# FMU_FMU_REV_1A.net
KiCad netlist of a schematic drawn in Altium Designer
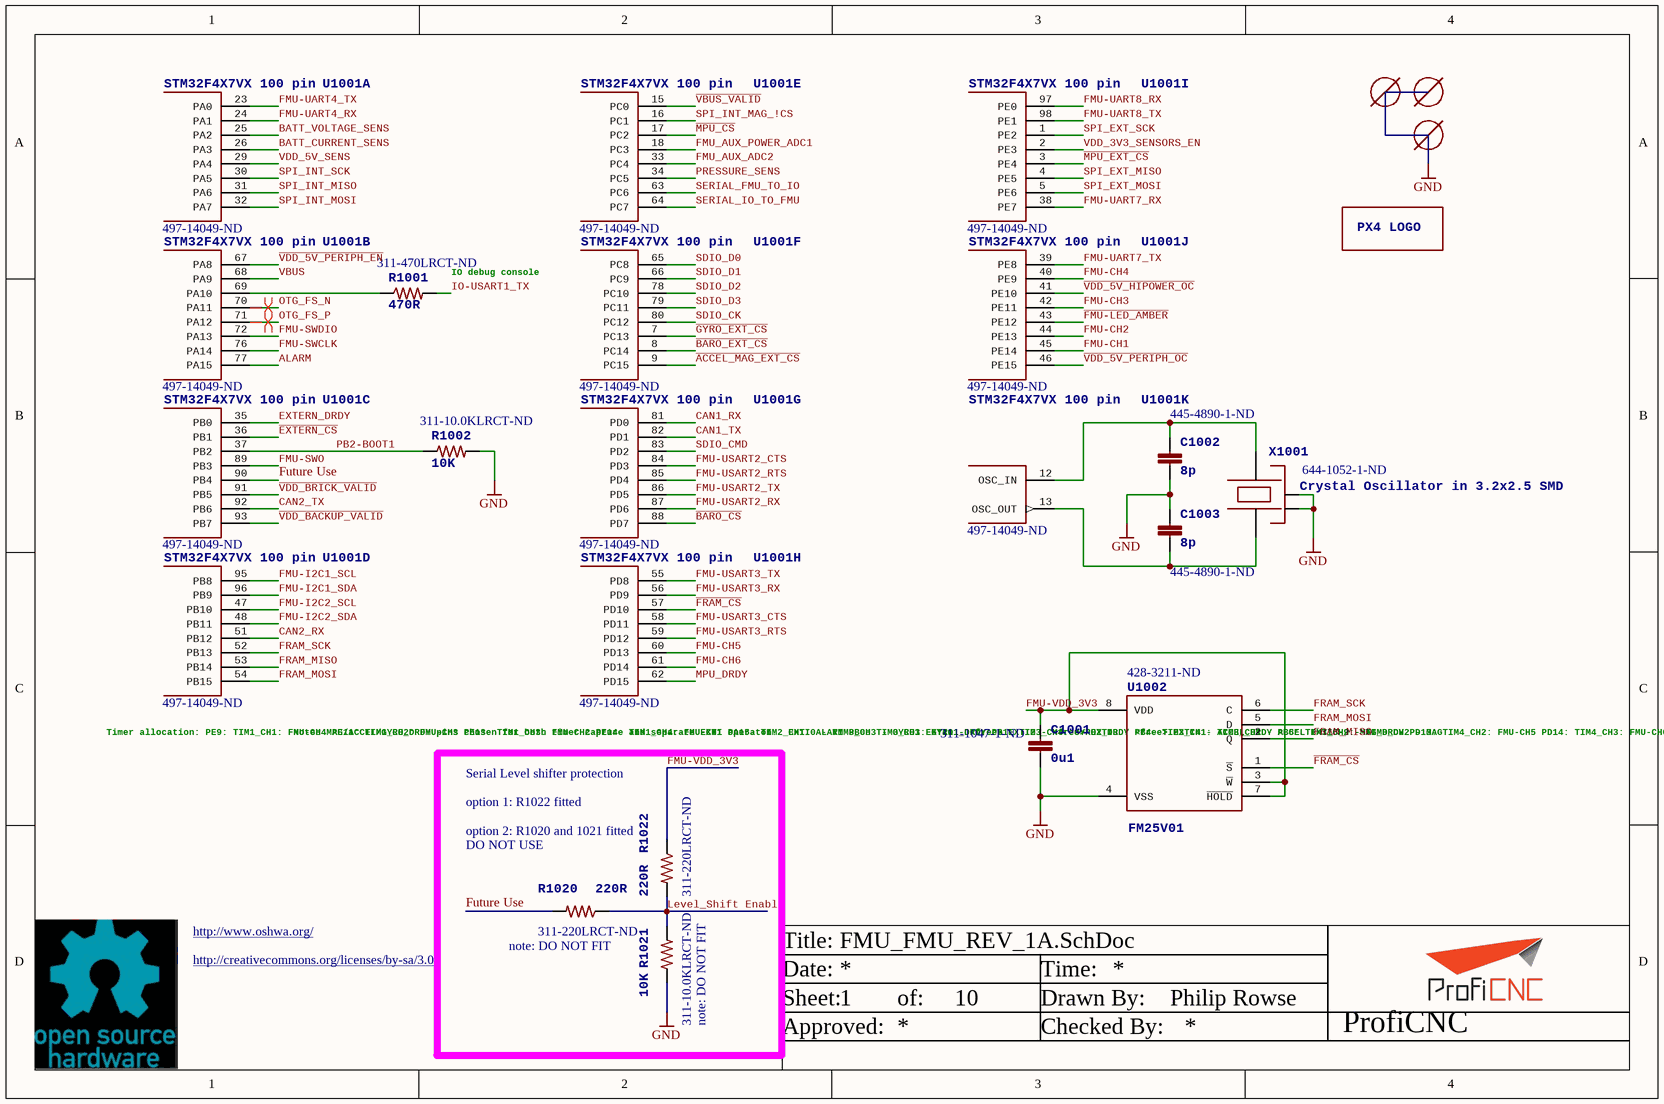
[diagram p0: FMU_FMU_REV_1A.SchDoc]

(export (version "E")
  (design (tool "Eeschema 10.0.6"))
  (components
    (comp (ref "C1001")
      (value "0u1")
      (footprint "0402-CAP")
      (description "CAP CER 0.1UF 16V Y5V 0402")
      (fields
        (field (name "PARTNO") "CC0402ZRY5V7BB104")
        (field (name "SUPPLIER PART NUMBER 1") "311-1047-1-ND")
        (field (name "3DR_PARTNO") "ECM0700")
      )
      (libsource (lib "pixhawk2") (part "CAP0402"))
    )
    (comp (ref "C1002")
      (value "8p")
      (footprint "0402-CAP")
      (description "CAP CER 8PF 50V C0G 0402")
      (fields
        (field (name "PARTNO") "C1005C0G1H080C")
        (field (name "SUPPLIER PART NUMBER 1") "445-4890-1-ND")
        (field (name "3DR_PARTNO") "ECM0710")
      )
      (libsource (lib "pixhawk2") (part "CAP0402"))
    )
    (comp (ref "C1003")
      (value "8p")
      (footprint "0402-CAP")
      (description "CAP CER 8PF 50V C0G 0402")
      (fields
        (field (name "PARTNO") "C1005C0G1H080C")
        (field (name "SUPPLIER PART NUMBER 1") "445-4890-1-ND")
        (field (name "3DR_PARTNO") "ECM0710")
      )
      (libsource (lib "pixhawk2") (part "CAP0402"))
    )
    (comp (ref "M3_MOUNT1001")
      (value "MOUNT-HOLE1.8MM")
      (footprint "MOUNT-HOLE1.8")
      (libsource (lib "pixhawk2") (part "MOUNT-HOLE1.8MM"))
    )
    (comp (ref "M3_MOUNT1003")
      (value "MOUNT-HOLE1.8MM")
      (footprint "MOUNT-HOLE1.8")
      (libsource (lib "pixhawk2") (part "MOUNT-HOLE1.8MM"))
    )
    (comp (ref "M3_MOUNT1004")
      (value "MOUNT-HOLE1.8MM")
      (footprint "MOUNT-HOLE1.8")
      (libsource (lib "pixhawk2") (part "MOUNT-HOLE1.8MM"))
    )
    (comp (ref "R1001")
      (value "470R")
      (footprint "0402-RES")
      (description "RES 470 OHM 1/16W 1% 0402 SMD")
      (fields
        (field (name "PARTNO") "RC0402FR-07470RL")
        (field (name "SUPPLIER PART NUMBER 1") "311-470LRCT-ND")
        (field (name "3DR_PARTNO") "ECM0823")
      )
      (libsource (lib "pixhawk2") (part "RESISTOR0402-RES"))
    )
    (comp (ref "R1002")
      (value "10K")
      (footprint "0402-RES")
      (description "RES 10K OHM 1/16W 1% 0402 SMD")
      (fields
        (field (name "PARTNO") "RC0402FR-0710KL")
        (field (name "SUPPLIER PART NUMBER 1") "311-10.0KLRCT-ND")
        (field (name "3DR_PARTNO") "ECM0800")
      )
      (libsource (lib "pixhawk2") (part "RESISTOR0402-RES"))
    )
    (comp (ref "R1020")
      (value "220R")
      (footprint "0402-RES")
      (description "RES 220 OHM 1/16W 1% 0402 SMD")
      (fields
        (field (name "PARTNO") "RC0402FR-07220RL")
        (field (name "SUPPLIER PART NUMBER 1") "311-220LRCT-ND")
        (field (name "3DR_PARTNO") "ECM0821")
        (field (name "NOTE") "DO NOT FIT")
      )
      (libsource (lib "pixhawk2") (part "RESISTOR0402-RES"))
    )
    (comp (ref "R1021")
      (value "10K")
      (footprint "0402-RES")
      (description "RES 10K OHM 1/16W 1% 0402 SMD")
      (fields
        (field (name "PARTNO") "RC0402FR-0710KL")
        (field (name "SUPPLIER PART NUMBER 1") "311-10.0KLRCT-ND")
        (field (name "3DR_PARTNO") "ECM0800")
        (field (name "NOTE") "DO NOT FIT")
      )
      (libsource (lib "pixhawk2") (part "RESISTOR0402-RES"))
    )
    (comp (ref "R1022")
      (value "220R")
      (footprint "0402-RES")
      (description "RES 220 OHM 1/16W 1% 0402 SMD")
      (fields
        (field (name "PARTNO") "RC0402FR-07220RL")
        (field (name "SUPPLIER PART NUMBER 1") "311-220LRCT-ND")
        (field (name "3DR_PARTNO") "ECM0821")
      )
      (libsource (lib "pixhawk2") (part "RESISTOR0402-RES"))
    )
    (comp (ref "U$4")
      (value "PX4-LOGO-10MM")
      (footprint "PX4-LOGO-10MM")
      (fields (field (name "PX4 LOGO") "PX4 LOGO"))
      (libsource (lib "pixhawk2") (part "PX4-LOGO-10MM"))
    )
    (comp (ref "U1001")
      (value "STM32F4X7VX 100 pin")
      (footprint "TQFP100")
      (description "REV 3 Silicon or later IC MCU ARM 2MB FLASH 100LQFP")
      (fields (field (name "SUPPLIER PART NUMBER 1") "497-14049-ND") (field (name "3DR_PARTNO") "ECM0841"))
      (libsource (lib "pixhawk2") (part "STM32F4X7VX"))
    )
    (comp (ref "U1002")
      (value "FM25V01")
      (footprint "SO08")
      (description "IC FRAM 128KBIT 40MHZ 8SOIC")
      (fields
        (field (name "PARTNO") "FM25V01-G")
        (field (name "SUPPLIER PART NUMBER 1") "428-3211-ND")
        (field (name "3DR_PARTNO") "ECM0826")
      )
      (libsource (lib "pixhawk2") (part "FM25V01"))
    )
    (comp (ref "X1001")
      (value "Crystal Oscillator in 3.2x2.5 SMD")
      (footprint "OSCILLATOR-3.2X2.5")
      (description "CRYSTAL 24MHZ 8PF SMD")
      (fields
        (field (name "SUPPLIER PART NUMBER 1") "644-1052-1-ND")
        (field (name "3DR_PARTNO") "ECM0708")
        (field (name "PARTNO") "NX3225SA-24.000MHZ-STD-CSR-1")
      )
      (libsource (lib "pixhawk2") (part "OSCILLATOR-3.2X2.5"))
    )
  )
  (nets
    (net (code "1") (name "/ALARM") (class "Default")
      (node (ref "U1001") (pin "77") (pinfunction "PA15_77") (pintype "passive"))
    )
    (net (code "2") (name "/BATT_CURRENT_SENS") (class "Default")
      (node (ref "U1001") (pin "26") (pinfunction "PA3_26") (pintype "passive"))
    )
    (net (code "3") (name "/BATT_VOLTAGE_SENS") (class "Default")
      (node (ref "U1001") (pin "25") (pinfunction "PA2_25") (pintype "passive"))
    )
    (net (code "4") (name "/CAN1_RX") (class "Default")
      (node (ref "U1001") (pin "81") (pinfunction "PD0_81") (pintype "passive"))
    )
    (net (code "5") (name "/CAN1_TX") (class "Default")
      (node (ref "U1001") (pin "82") (pinfunction "PD1_82") (pintype "passive"))
    )
    (net (code "6") (name "/CAN2_RX") (class "Default")
      (node (ref "U1001") (pin "51") (pinfunction "PB12_51") (pintype "passive"))
    )
    (net (code "7") (name "/CAN2_TX") (class "Default")
      (node (ref "U1001") (pin "92") (pinfunction "PB6_92") (pintype "passive"))
    )
    (net (code "8") (name "/EXTERN_DRDY") (class "Default")
      (node (ref "U1001") (pin "35") (pinfunction "PB0_35") (pintype "passive"))
    )
    (net (code "9") (name "/FMU-CH1") (class "Default")
      (node (ref "U1001") (pin "45") (pinfunction "PE14_45") (pintype "passive"))
    )
    (net (code "10") (name "/FMU-CH2") (class "Default")
      (node (ref "U1001") (pin "44") (pinfunction "PE13_44") (pintype "passive"))
    )
    (net (code "11") (name "/FMU-CH3") (class "Default")
      (node (ref "U1001") (pin "42") (pinfunction "PE11_42") (pintype "passive"))
    )
    (net (code "12") (name "/FMU-CH4") (class "Default")
      (node (ref "U1001") (pin "40") (pinfunction "PE9_40") (pintype "passive"))
    )
    (net (code "13") (name "/FMU-CH5") (class "Default")
      (node (ref "U1001") (pin "60") (pinfunction "PD13_60") (pintype "passive"))
    )
    (net (code "14") (name "/FMU-CH6") (class "Default")
      (node (ref "U1001") (pin "61") (pinfunction "PD14_61") (pintype "passive"))
    )
    (net (code "15") (name "/FMU-I2C1_SCL") (class "Default")
      (node (ref "U1001") (pin "95") (pinfunction "PB8_95") (pintype "passive"))
    )
    (net (code "16") (name "/FMU-I2C1_SDA") (class "Default")
      (node (ref "U1001") (pin "96") (pinfunction "PB9_96") (pintype "passive"))
    )
    (net (code "17") (name "/FMU-I2C2_SCL") (class "Default")
      (node (ref "U1001") (pin "47") (pinfunction "PB10_47") (pintype "passive"))
    )
    (net (code "18") (name "/FMU-I2C2_SDA") (class "Default")
      (node (ref "U1001") (pin "48") (pinfunction "PB11_48") (pintype "passive"))
    )
    (net (code "19") (name "/FMU-SWCLK") (class "Default")
      (node (ref "U1001") (pin "76") (pinfunction "PA14_76") (pintype "passive"))
    )
    (net (code "20") (name "/FMU-SWDIO") (class "Default")
      (node (ref "U1001") (pin "72") (pinfunction "PA13_72") (pintype "passive"))
    )
    (net (code "21") (name "/FMU-SWO") (class "Default")
      (node (ref "U1001") (pin "89") (pinfunction "PB3_89") (pintype "passive"))
    )
    (net (code "22") (name "/FMU-UART4_RX") (class "Default")
      (node (ref "U1001") (pin "24") (pinfunction "PA1_24") (pintype "passive"))
    )
    (net (code "23") (name "/FMU-UART4_TX") (class "Default")
      (node (ref "U1001") (pin "23") (pinfunction "PA0_23") (pintype "passive"))
    )
    (net (code "24") (name "/FMU-UART7_RX") (class "Default")
      (node (ref "U1001") (pin "38") (pinfunction "PE7_38") (pintype "passive"))
    )
    (net (code "25") (name "/FMU-UART7_TX") (class "Default")
      (node (ref "U1001") (pin "39") (pinfunction "PE8_39") (pintype "passive"))
    )
    (net (code "26") (name "/FMU-UART8_RX") (class "Default")
      (node (ref "U1001") (pin "97") (pinfunction "PE0_97") (pintype "passive"))
    )
    (net (code "27") (name "/FMU-UART8_TX") (class "Default")
      (node (ref "U1001") (pin "98") (pinfunction "PE1_98") (pintype "passive"))
    )
    (net (code "28") (name "/FMU-USART2_CTS") (class "Default")
      (node (ref "U1001") (pin "84") (pinfunction "PD3_84") (pintype "passive"))
    )
    (net (code "29") (name "/FMU-USART2_RTS") (class "Default")
      (node (ref "U1001") (pin "85") (pinfunction "PD4_85") (pintype "passive"))
    )
    (net (code "30") (name "/FMU-USART2_RX") (class "Default")
      (node (ref "U1001") (pin "87") (pinfunction "PD6_87") (pintype "passive"))
    )
    (net (code "31") (name "/FMU-USART2_TX") (class "Default")
      (node (ref "U1001") (pin "86") (pinfunction "PD5_86") (pintype "passive"))
    )
    (net (code "32") (name "/FMU-USART3_CTS") (class "Default")
      (node (ref "U1001") (pin "58") (pinfunction "PD11_58") (pintype "passive"))
    )
    (net (code "33") (name "/FMU-USART3_RTS") (class "Default")
      (node (ref "U1001") (pin "59") (pinfunction "PD12_59") (pintype "passive"))
    )
    (net (code "34") (name "/FMU-USART3_RX") (class "Default")
      (node (ref "U1001") (pin "56") (pinfunction "PD9_56") (pintype "passive"))
    )
    (net (code "35") (name "/FMU-USART3_TX") (class "Default")
      (node (ref "U1001") (pin "55") (pinfunction "PD8_55") (pintype "passive"))
    )
    (net (code "36") (name "/FMU-VDD_3V3") (class "Default")
      (node (ref "C1001") (pin "P$1") (pinfunction "1_P$1") (pintype "passive"))
      (node (ref "R1022") (pin "P$1") (pinfunction "1_P$1") (pintype "passive"))
      (node (ref "U1002") (pin "3") (pinfunction "~{W}_3") (pintype "passive"))
      (node (ref "U1002") (pin "7") (pinfunction "~{HOLD}_7") (pintype "passive"))
      (node (ref "U1002") (pin "8") (pinfunction "VDD_8") (pintype "passive"))
    )
    (net (code "37") (name "/FMU_AUX_ADC2") (class "Default")
      (node (ref "U1001") (pin "33") (pinfunction "PC4_33") (pintype "passive"))
    )
    (net (code "38") (name "/FMU_AUX_POWER_ADC1") (class "Default")
      (node (ref "U1001") (pin "18") (pinfunction "PC3_18") (pintype "passive"))
    )
    (net (code "39") (name "/FRAM_MISO") (class "Default")
      (node (ref "U1001") (pin "53") (pinfunction "PB14_53") (pintype "passive"))
      (node (ref "U1002") (pin "2") (pinfunction "Q_2") (pintype "passive"))
    )
    (net (code "40") (name "/FRAM_MOSI") (class "Default")
      (node (ref "U1001") (pin "54") (pinfunction "PB15_54") (pintype "passive"))
      (node (ref "U1002") (pin "5") (pinfunction "D_5") (pintype "passive"))
    )
    (net (code "41") (name "/FRAM_SCK") (class "Default")
      (node (ref "U1001") (pin "52") (pinfunction "PB13_52") (pintype "passive"))
      (node (ref "U1002") (pin "6") (pinfunction "C_6") (pintype "passive"))
    )
    (net (code "42") (name "/Future Use") (class "Default")
      (node (ref "R1020") (pin "P$2") (pinfunction "2_P$2") (pintype "passive"))
      (node (ref "U1001") (pin "90") (pinfunction "PB4_90") (pintype "passive"))
    )
    (net (code "43") (name "/IO-USART1_TX") (class "Default")
      (node (ref "R1001") (pin "P$2") (pinfunction "2_P$2") (pintype "passive"))
    )
    (net (code "44") (name "/Level_Shift Enable") (class "Default")
      (node (ref "R1020") (pin "P$1") (pinfunction "1_P$1") (pintype "passive"))
      (node (ref "R1021") (pin "P$2") (pinfunction "2_P$2") (pintype "passive"))
      (node (ref "R1022") (pin "P$2") (pinfunction "2_P$2") (pintype "passive"))
    )
    (net (code "45") (name "/MPU_DRDY") (class "Default")
      (node (ref "U1001") (pin "62") (pinfunction "PD15_62") (pintype "passive"))
    )
    (net (code "46") (name "/OTG_FS_N") (class "Default")
      (node (ref "U1001") (pin "70") (pinfunction "PA11_70") (pintype "passive"))
    )
    (net (code "47") (name "/OTG_FS_P") (class "Default")
      (node (ref "U1001") (pin "71") (pinfunction "PA12_71") (pintype "passive"))
    )
    (net (code "48") (name "/PB2-BOOT1") (class "Default")
      (node (ref "R1002") (pin "P$1") (pinfunction "1_P$1") (pintype "passive"))
      (node (ref "U1001") (pin "37") (pinfunction "PB2_37") (pintype "passive"))
    )
    (net (code "49") (name "/PRESSURE_SENS") (class "Default")
      (node (ref "U1001") (pin "34") (pinfunction "PC5_34") (pintype "passive"))
    )
    (net (code "50") (name "/SDIO_CK") (class "Default")
      (node (ref "U1001") (pin "80") (pinfunction "PC12_80") (pintype "passive"))
    )
    (net (code "51") (name "/SDIO_CMD") (class "Default")
      (node (ref "U1001") (pin "83") (pinfunction "PD2_83") (pintype "passive"))
    )
    (net (code "52") (name "/SDIO_D0") (class "Default")
      (node (ref "U1001") (pin "65") (pinfunction "PC8_65") (pintype "passive"))
    )
    (net (code "53") (name "/SDIO_D1") (class "Default")
      (node (ref "U1001") (pin "66") (pinfunction "PC9_66") (pintype "passive"))
    )
    (net (code "54") (name "/SDIO_D2") (class "Default")
      (node (ref "U1001") (pin "78") (pinfunction "PC10_78") (pintype "passive"))
    )
    (net (code "55") (name "/SDIO_D3") (class "Default")
      (node (ref "U1001") (pin "79") (pinfunction "PC11_79") (pintype "passive"))
    )
    (net (code "56") (name "/SERIAL_FMU_TO_IO") (class "Default")
      (node (ref "U1001") (pin "63") (pinfunction "PC6_63") (pintype "passive"))
    )
    (net (code "57") (name "/SERIAL_IO_TO_FMU") (class "Default")
      (node (ref "U1001") (pin "64") (pinfunction "PC7_64") (pintype "passive"))
    )
    (net (code "58") (name "/SPI_EXT_MISO") (class "Default")
      (node (ref "U1001") (pin "4") (pinfunction "PE5_4") (pintype "passive"))
    )
    (net (code "59") (name "/SPI_EXT_MOSI") (class "Default")
      (node (ref "U1001") (pin "5") (pinfunction "PE6_5") (pintype "passive"))
    )
    (net (code "60") (name "/SPI_EXT_SCK") (class "Default")
      (node (ref "U1001") (pin "1") (pinfunction "PE2_1") (pintype "passive"))
    )
    (net (code "61") (name "/SPI_INT_MAG_!CS") (class "Default")
      (node (ref "U1001") (pin "16") (pinfunction "PC1_16") (pintype "passive"))
    )
    (net (code "62") (name "/SPI_INT_MISO") (class "Default")
      (node (ref "U1001") (pin "31") (pinfunction "PA6_31") (pintype "passive"))
    )
    (net (code "63") (name "/SPI_INT_MOSI") (class "Default")
      (node (ref "U1001") (pin "32") (pinfunction "PA7_32") (pintype "passive"))
    )
    (net (code "64") (name "/SPI_INT_SCK") (class "Default")
      (node (ref "U1001") (pin "30") (pinfunction "PA5_30") (pintype "passive"))
    )
    (net (code "65") (name "/VBUS") (class "Default")
      (node (ref "U1001") (pin "68") (pinfunction "PA9_68") (pintype "passive"))
    )
    (net (code "66") (name "/VDD_3V3_SENSORS_EN") (class "Default")
      (node (ref "U1001") (pin "2") (pinfunction "PE3_2") (pintype "passive"))
    )
    (net (code "67") (name "/VDD_5V_SENS") (class "Default")
      (node (ref "U1001") (pin "29") (pinfunction "PA4_29") (pintype "passive"))
    )
    (net (code "68") (name "/~{ACCEL_MAG_EXT_CS}") (class "Default")
      (node (ref "U1001") (pin "9") (pinfunction "PC15_9") (pintype "passive"))
    )
    (net (code "69") (name "/~{BARO_CS}") (class "Default")
      (node (ref "U1001") (pin "88") (pinfunction "PD7_88") (pintype "passive"))
    )
    (net (code "70") (name "/~{BARO_EXT_CS}") (class "Default")
      (node (ref "U1001") (pin "8") (pinfunction "PC14_8") (pintype "passive"))
    )
    (net (code "71") (name "/~{EXTERN_CS}") (class "Default")
      (node (ref "U1001") (pin "36") (pinfunction "PB1_36") (pintype "passive"))
    )
    (net (code "72") (name "/~{FMU-LED_AMBER}") (class "Default")
      (node (ref "U1001") (pin "43") (pinfunction "PE12_43") (pintype "passive"))
    )
    (net (code "73") (name "/~{FRAM_CS}") (class "Default")
      (node (ref "U1001") (pin "57") (pinfunction "PD10_57") (pintype "passive"))
      (node (ref "U1002") (pin "1") (pinfunction "~{S}_1") (pintype "passive"))
    )
    (net (code "74") (name "/~{GYRO_EXT_CS}") (class "Default")
      (node (ref "U1001") (pin "7") (pinfunction "PC13_7") (pintype "passive"))
    )
    (net (code "75") (name "/~{MPU_CS}") (class "Default")
      (node (ref "U1001") (pin "17") (pinfunction "PC2_17") (pintype "passive"))
    )
    (net (code "76") (name "/~{MPU_EXT_CS}") (class "Default")
      (node (ref "U1001") (pin "3") (pinfunction "PE4_3") (pintype "passive"))
    )
    (net (code "77") (name "/~{VBUS_VALID}") (class "Default")
      (node (ref "U1001") (pin "15") (pinfunction "PC0_15") (pintype "passive"))
    )
    (net (code "78") (name "/~{VDD_5V_HIPOWER_OC}") (class "Default")
      (node (ref "U1001") (pin "41") (pinfunction "PE10_41") (pintype "passive"))
    )
    (net (code "79") (name "/~{VDD_5V_PERIPH_EN}") (class "Default")
      (node (ref "U1001") (pin "67") (pinfunction "PA8_67") (pintype "passive"))
    )
    (net (code "80") (name "/~{VDD_5V_PERIPH_OC}") (class "Default")
      (node (ref "U1001") (pin "46") (pinfunction "PE15_46") (pintype "passive"))
    )
    (net (code "81") (name "/~{VDD_BACKUP_VALID}") (class "Default")
      (node (ref "U1001") (pin "93") (pinfunction "PB7_93") (pintype "passive"))
    )
    (net (code "82") (name "/~{VDD_BRICK_VALID}") (class "Default")
      (node (ref "U1001") (pin "91") (pinfunction "PB5_91") (pintype "passive"))
    )
    (net (code "83") (name "GND") (class "Default")
      (node (ref "C1001") (pin "P$2") (pinfunction "2_P$2") (pintype "passive"))
      (node (ref "C1002") (pin "P$2") (pinfunction "2_P$2") (pintype "passive"))
      (node (ref "C1003") (pin "P$1") (pinfunction "1_P$1") (pintype "passive"))
      (node (ref "R1002") (pin "P$2") (pinfunction "2_P$2") (pintype "passive"))
      (node (ref "R1021") (pin "P$1") (pinfunction "1_P$1") (pintype "passive"))
      (node (ref "U1002") (pin "4") (pinfunction "VSS_4") (pintype "passive"))
      (node (ref "X1001") (pin "2") (pinfunction "NC_2_2") (pintype "open_emitter"))
      (node (ref "X1001") (pin "4") (pinfunction "NC_4_4") (pintype "open_emitter"))
    )
    (net (code "84") (name "Net-(C1002-1)") (class "Default")
      (node (ref "C1002") (pin "P$1") (pinfunction "1_P$1") (pintype "passive"))
      (node (ref "U1001") (pin "12") (pinfunction "OSC_IN_12") (pintype "passive"))
      (node (ref "X1001") (pin "3") (pinfunction "3_3") (pintype "passive"))
    )
    (net (code "85") (name "Net-(C1003-2)") (class "Default")
      (node (ref "C1003") (pin "P$2") (pinfunction "2_P$2") (pintype "passive"))
      (node (ref "U1001") (pin "13") (pinfunction "OSC_OUT_13") (pintype "output"))
      (node (ref "X1001") (pin "1") (pinfunction "1_1") (pintype "passive"))
    )
    (net (code "86") (name "Net-(R1001-1)") (class "Default")
      (node (ref "R1001") (pin "P$1") (pinfunction "1_P$1") (pintype "passive"))
      (node (ref "U1001") (pin "69") (pinfunction "PA10_69") (pintype "passive"))
    )
  )
)
